# DRV8301_LaunchPad.net
KiCad netlist of a schematic drawn in Altium Designer
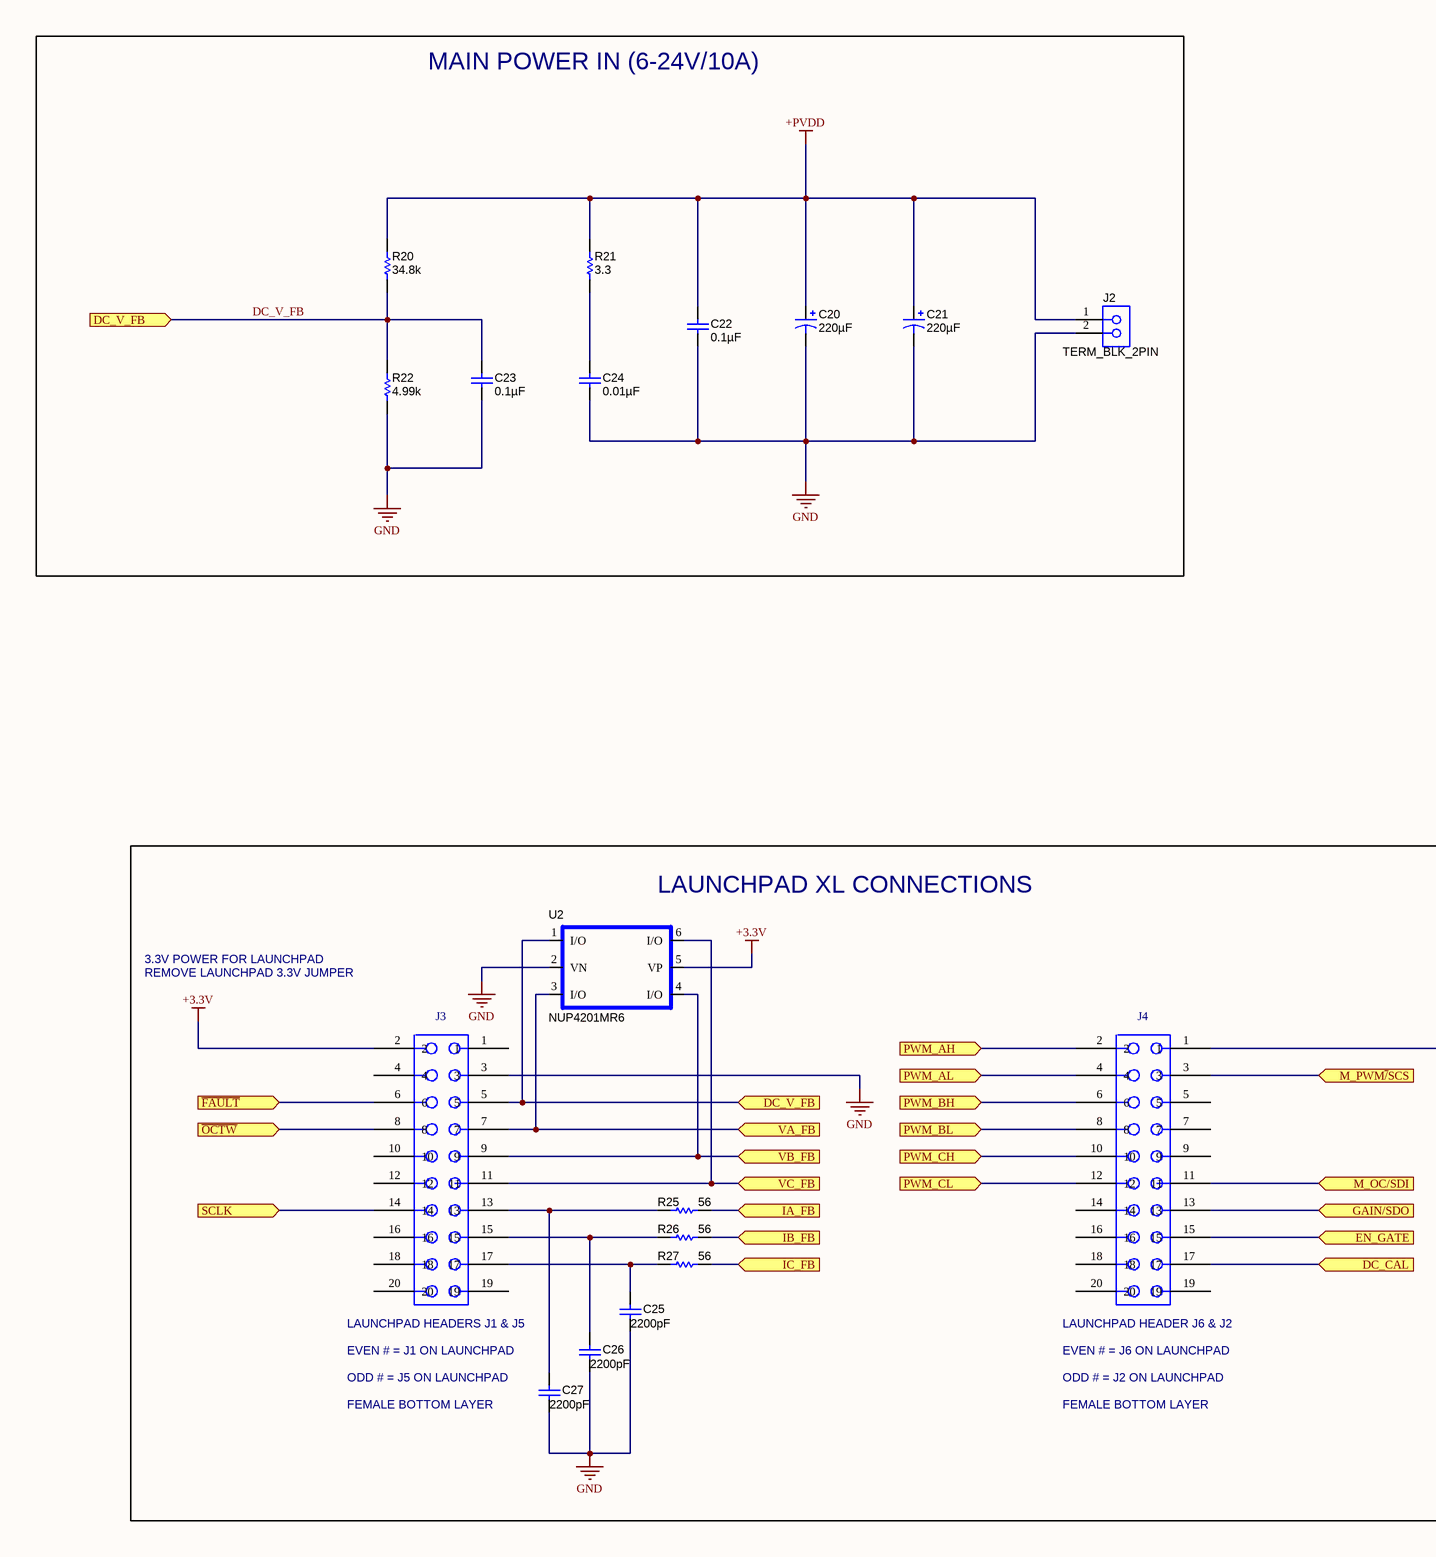
[diagram p0: DRV8301_LaunchPad.SchDoc, left]
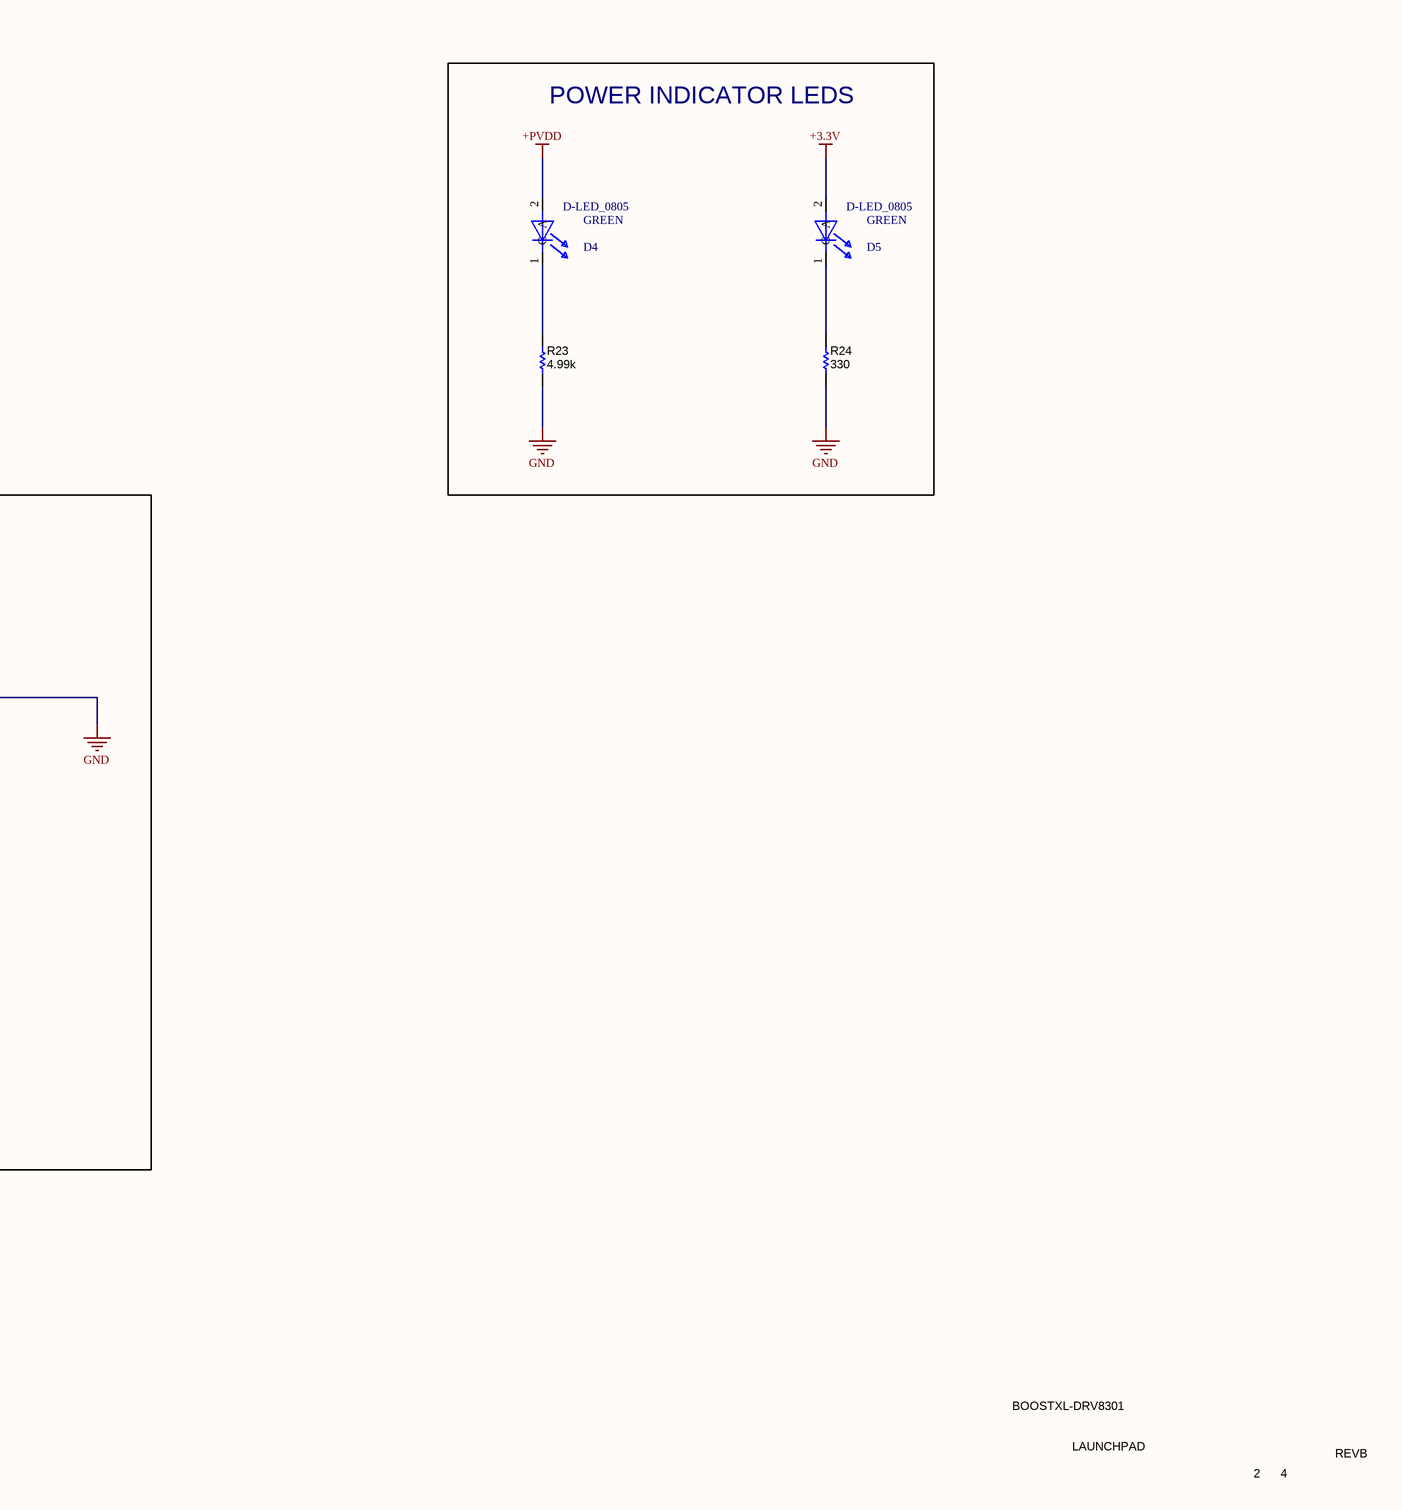
[diagram p1: DRV8301_LaunchPad.SchDoc, right]

(export (version "E")
  (design (tool "Eeschema 10.0.6"))
  (components
    (comp (ref "C20")
      (value "EEE-FC1H221P")
      (footprint "SM_RADIAL_G")
      (description "CAP, AL, 220uF, 50V, +/-20%, 0.3 ohm, SMD")
      (fields
        (field (name "VALUEDISPLAYED") "220µF")
        (field (name "MANUFACTURER") "Panasonic")
        (field (name "PUBLISHER") "Texas Instruments")
      )
      (libsource (lib "Capacitor_Aluminum") (part "EEE-FC1H221P"))
    )
    (comp (ref "C21")
      (value "EEE-FC1H221P")
      (footprint "SM_RADIAL_G")
      (description "CAP, AL, 220uF, 50V, +/-20%, 0.3 ohm, SMD")
      (fields
        (field (name "VALUEDISPLAYED") "220µF")
        (field (name "MANUFACTURER") "Panasonic")
        (field (name "PUBLISHER") "Texas Instruments")
      )
      (libsource (lib "Capacitor_Aluminum") (part "EEE-FC1H221P"))
    )
    (comp (ref "C22")
      (value "GRM188R72A104KA35D")
      (footprint "0603L")
      (description "CAP, CERM, 0.1uF, 100V, +/-10%, X7R, 0603")
      (fields
        (field (name "VALUEDISPLAYED") "0.1µF")
        (field (name "MANUFACTURER") "MuRata")
        (field (name "PUBLISHER") "Texas Instruments")
      )
      (libsource (lib "Capacitor_Ceramic") (part "GRM188R72A104KA35D"))
    )
    (comp (ref "C23")
      (value "C0603C104J4RACTU")
      (footprint "0603L")
      (description "CAP, CERM, 0.1uF, 16V, +/-5%, X7R, 0603")
      (fields
        (field (name "VALUEDISPLAYED") "0.1µF")
        (field (name "MANUFACTURER") "Kemet")
        (field (name "PUBLISHER") "Texas Instruments")
      )
      (libsource (lib "Capacitor_Ceramic") (part "C0603C104J4RACTU"))
    )
    (comp (ref "C24")
      (value "C1608X7R2A103K")
      (footprint "0603L")
      (description "CAP, CERM, 0.01uF, 100V, +/-10%, X7R, 0603")
      (fields
        (field (name "VALUEDISPLAYED") "0.01µF")
        (field (name "MANUFACTURER") "TDK")
        (field (name "PUBLISHER") "Texas Instruments")
      )
      (libsource (lib "Capacitor_Ceramic") (part "C1608X7R2A103K"))
    )
    (comp (ref "C25")
      (value "GRM188R71C222KA01D")
      (footprint "0603L")
      (description "CAP, CERM, 2200pF, 16V, +/-10%, X7R, 0603")
      (fields
        (field (name "VALUEDISPLAYED") "2200pF")
        (field (name "MANUFACTURER") "MuRata")
        (field (name "PUBLISHER") "Texas Instruments")
      )
      (libsource (lib "Capacitor_Ceramic") (part "GRM188R71C222KA01D"))
    )
    (comp (ref "C26")
      (value "GRM188R71C222KA01D")
      (footprint "0603L")
      (description "CAP, CERM, 2200pF, 16V, +/-10%, X7R, 0603")
      (fields
        (field (name "VALUEDISPLAYED") "2200pF")
        (field (name "MANUFACTURER") "MuRata")
        (field (name "PUBLISHER") "Texas Instruments")
      )
      (libsource (lib "Capacitor_Ceramic") (part "GRM188R71C222KA01D"))
    )
    (comp (ref "C27")
      (value "GRM188R71C222KA01D")
      (footprint "0603L")
      (description "CAP, CERM, 2200pF, 16V, +/-10%, X7R, 0603")
      (fields
        (field (name "VALUEDISPLAYED") "2200pF")
        (field (name "MANUFACTURER") "MuRata")
        (field (name "PUBLISHER") "Texas Instruments")
      )
      (libsource (lib "Capacitor_Ceramic") (part "GRM188R71C222KA01D"))
    )
    (comp (ref "D4")
      (value "D-LED_0805")
      (footprint "LED_0805")
      (description "LED THIN 565NM GRN DIFF 0805 SMD")
      (fields
        (field (name "PARTNUMBER") "SML-LXT0805GW-TR")
        (field (name "ALTIUM_VALUE") "GREEN")
        (field (name "MANUFACTURER") "Lumex Opto/Components Inc")
      )
      (libsource (lib "*") (part "D-LED_0805"))
    )
    (comp (ref "D5")
      (value "D-LED_0805")
      (footprint "LED_0805")
      (description "LED THIN 565NM GRN DIFF 0805 SMD")
      (fields
        (field (name "PARTNUMBER") "SML-LXT0805GW-TR")
        (field (name "ALTIUM_VALUE") "GREEN")
        (field (name "MANUFACTURER") "Lumex Opto/Components Inc")
      )
      (libsource (lib "*") (part "D-LED_0805"))
    )
    (comp (ref "J2")
      (value "TERM_BLK_2PIN")
      (footprint "CONN_ED120-2DS")
      (description "TERMINAL BLOCK 5.08MM VERT 2POS")
      (fields
        (field (name "PARTNUMBER") "OSTTA024163")
        (field (name "MANUFACTURER") "On-Shore Technology")
        (field (name "PUBLISHER") "Texas Instruments")
      )
      (libsource (lib "Connectors") (part "ED120/2DS"))
    )
    (comp (ref "J3")
      (value "HEADER_NPTC202KFM")
      (description "CONN RCPT 20POS .100 DL STR SMD")
      (fields (field (name "PARTNUMBER") "89898-310ALF") (field (name "MANUFACTURER") "FCI"))
      (libsource (lib "*") (part "HEADER_NPTC202KFM"))
    )
    (comp (ref "J4")
      (value "HEADER_NPTC202KFM")
      (description "CONN RCPT 20POS .100 DL STR SMD")
      (fields (field (name "PARTNUMBER") "89898-310ALF") (field (name "MANUFACTURER") "FCI"))
      (libsource (lib "*") (part "HEADER_NPTC202KFM"))
    )
    (comp (ref "R20")
      (value "34.8k")
      (footprint "0603L")
      (description "RES, 34.8k ohm, 1%, 0.1W, 0603")
      (fields
        (field (name "PARTNUMBER") "CRCW060334K8FKEA")
        (field (name "MANUFACTURER") "Vishay-Dale")
        (field (name "PUBLISHER") "Texas Instruments")
      )
      (libsource (lib "Resistor_0603") (part "CRCW060334K8FKEA"))
    )
    (comp (ref "R21")
      (value "3.3")
      (footprint "1206L")
      (description "RES, 3.3 ohm, 5%, 0.25W, 1206")
      (fields
        (field (name "PARTNUMBER") "CRCW12063R30JNEA")
        (field (name "MANUFACTURER") "Vishay-Dale")
        (field (name "PUBLISHER") "Texas Instruments")
      )
      (libsource (lib "Resistor_1206") (part "CRCW12063R30JNEA"))
    )
    (comp (ref "R22")
      (value "4.99k")
      (footprint "0603L")
      (description "RES, 4.99k ohm, 1%, 0.1W, 0603")
      (fields
        (field (name "PARTNUMBER") "CRCW06034K99FKEA")
        (field (name "MANUFACTURER") "Vishay-Dale")
        (field (name "PUBLISHER") "Texas Instruments")
      )
      (libsource (lib "Resistor_0603") (part "CRCW06034K99FKEA"))
    )
    (comp (ref "R23")
      (value "4.99k")
      (footprint "0603L")
      (description "RES, 4.99k ohm, 1%, 0.1W, 0603")
      (fields
        (field (name "PARTNUMBER") "CRCW06034K99FKEA")
        (field (name "MANUFACTURER") "Vishay-Dale")
        (field (name "PUBLISHER") "Texas Instruments")
      )
      (libsource (lib "Resistor_0603") (part "CRCW06034K99FKEA"))
    )
    (comp (ref "R24")
      (value "330")
      (footprint "0603L")
      (description "RES, 330 ohm, 5%, 0.1W, 0603")
      (fields
        (field (name "PARTNUMBER") "CRCW0603330RJNEA")
        (field (name "MANUFACTURER") "Vishay-Dale")
        (field (name "PUBLISHER") "Texas Instruments")
      )
      (libsource (lib "Resistor_0603") (part "CRCW0603330RJNEA"))
    )
    (comp (ref "R25")
      (value "56")
      (footprint "0603L")
      (description "RES, 56 ohm, 5%, 0.1W, 0603")
      (fields
        (field (name "PARTNUMBER") "CRCW060356R0JNEA")
        (field (name "MANUFACTURER") "Vishay-Dale")
        (field (name "PUBLISHER") "Texas Instruments")
      )
      (libsource (lib "Resistor_0603") (part "CRCW060356R0JNEA"))
    )
    (comp (ref "R26")
      (value "56")
      (footprint "0603L")
      (description "RES, 56 ohm, 5%, 0.1W, 0603")
      (fields
        (field (name "PARTNUMBER") "CRCW060356R0JNEA")
        (field (name "MANUFACTURER") "Vishay-Dale")
        (field (name "PUBLISHER") "Texas Instruments")
      )
      (libsource (lib "Resistor_0603") (part "CRCW060356R0JNEA"))
    )
    (comp (ref "R27")
      (value "56")
      (footprint "0603L")
      (description "RES, 56 ohm, 5%, 0.1W, 0603")
      (fields
        (field (name "PARTNUMBER") "CRCW060356R0JNEA")
        (field (name "MANUFACTURER") "Vishay-Dale")
        (field (name "PUBLISHER") "Texas Instruments")
      )
      (libsource (lib "Resistor_0603") (part "CRCW060356R0JNEA"))
    )
    (comp (ref "U2")
      (value "NUP4201MR6")
      (footprint "SOT23-6")
      (description "IC,  500w 6v, Transient Voltage  Suppressors")
      (fields (field (name "MANUFACTURER") "On Semi"))
      (libsource (lib "PADSlegacy_PMP") (part "NUP4201MR6"))
    )
  )
  (nets
    (net (code "1") (name "+3.3V") (class "Default")
      (node (ref "D5") (pin "2") (pinfunction "A_2") (pintype "passive"))
      (node (ref "J3") (pin "2") (pinfunction "2_2") (pintype "passive"))
      (node (ref "U2") (pin "5") (pinfunction "VP_5") (pintype "passive"))
    )
    (net (code "2") (name "+PVDD") (class "Default")
      (node (ref "C20") (pin "1") (pinfunction "+_1") (pintype "passive"))
      (node (ref "C21") (pin "1") (pinfunction "+_1") (pintype "passive"))
      (node (ref "C22") (pin "1") (pinfunction "1_1") (pintype "passive"))
      (node (ref "D4") (pin "2") (pinfunction "A_2") (pintype "passive"))
      (node (ref "J2") (pin "1") (pinfunction "1_1") (pintype "passive"))
      (node (ref "R20") (pin "2") (pinfunction "2_2") (pintype "passive"))
      (node (ref "R21") (pin "2") (pinfunction "2_2") (pintype "passive"))
    )
    (net (code "3") (name "/DC_CAL") (class "Default")
      (node (ref "J4") (pin "17") (pinfunction "17_17") (pintype "passive"))
    )
    (net (code "4") (name "/DC_V_FB") (class "Default")
      (node (ref "C23") (pin "1") (pinfunction "1_1") (pintype "passive"))
      (node (ref "J3") (pin "5") (pinfunction "5_5") (pintype "passive"))
      (node (ref "R20") (pin "1") (pinfunction "1_1") (pintype "passive"))
      (node (ref "R22") (pin "2") (pinfunction "2_2") (pintype "passive"))
      (node (ref "U2") (pin "1") (pinfunction "I/O_1") (pintype "passive"))
    )
    (net (code "5") (name "/EN_GATE") (class "Default")
      (node (ref "J4") (pin "15") (pinfunction "15_15") (pintype "passive"))
    )
    (net (code "6") (name "/FAULT") (class "Default")
      (node (ref "J3") (pin "6") (pinfunction "6_6") (pintype "passive"))
    )
    (net (code "7") (name "/GAIN{slash}SDO") (class "Default")
      (node (ref "J4") (pin "13") (pinfunction "13_13") (pintype "passive"))
    )
    (net (code "8") (name "/IA_FB") (class "Default")
      (node (ref "R25") (pin "2") (pinfunction "2_2") (pintype "passive"))
    )
    (net (code "9") (name "/IB_FB") (class "Default")
      (node (ref "R26") (pin "2") (pinfunction "2_2") (pintype "passive"))
    )
    (net (code "10") (name "/IC_FB") (class "Default")
      (node (ref "R27") (pin "2") (pinfunction "2_2") (pintype "passive"))
    )
    (net (code "11") (name "/M_OC{slash}SDI") (class "Default")
      (node (ref "J4") (pin "11") (pinfunction "11_11") (pintype "passive"))
    )
    (net (code "12") (name "/M_PWM~{{slash}}SCS") (class "Default")
      (node (ref "J4") (pin "3") (pinfunction "3_3") (pintype "passive"))
    )
    (net (code "13") (name "/OCTW") (class "Default")
      (node (ref "J3") (pin "8") (pinfunction "8_8") (pintype "passive"))
    )
    (net (code "14") (name "/PWM_AH") (class "Default")
      (node (ref "J4") (pin "2") (pinfunction "2_2") (pintype "passive"))
    )
    (net (code "15") (name "/PWM_AL") (class "Default")
      (node (ref "J4") (pin "4") (pinfunction "4_4") (pintype "passive"))
    )
    (net (code "16") (name "/PWM_BH") (class "Default")
      (node (ref "J4") (pin "6") (pinfunction "6_6") (pintype "passive"))
    )
    (net (code "17") (name "/PWM_BL") (class "Default")
      (node (ref "J4") (pin "8") (pinfunction "8_8") (pintype "passive"))
    )
    (net (code "18") (name "/PWM_CH") (class "Default")
      (node (ref "J4") (pin "10") (pinfunction "10_10") (pintype "passive"))
    )
    (net (code "19") (name "/PWM_CL") (class "Default")
      (node (ref "J4") (pin "12") (pinfunction "12_12") (pintype "passive"))
    )
    (net (code "20") (name "/SCLK") (class "Default")
      (node (ref "J3") (pin "14") (pinfunction "14_14") (pintype "passive"))
    )
    (net (code "21") (name "/VA_FB") (class "Default")
      (node (ref "J3") (pin "7") (pinfunction "7_7") (pintype "passive"))
      (node (ref "U2") (pin "3") (pinfunction "I/O_3") (pintype "passive"))
    )
    (net (code "22") (name "/VB_FB") (class "Default")
      (node (ref "J3") (pin "9") (pinfunction "9_9") (pintype "passive"))
      (node (ref "U2") (pin "4") (pinfunction "I/O_4") (pintype "passive"))
    )
    (net (code "23") (name "/VC_FB") (class "Default")
      (node (ref "J3") (pin "11") (pinfunction "11_11") (pintype "passive"))
      (node (ref "U2") (pin "6") (pinfunction "I/O_6") (pintype "passive"))
    )
    (net (code "24") (name "GND") (class "Default")
      (node (ref "C20") (pin "2") (pinfunction "-_2") (pintype "passive"))
      (node (ref "C21") (pin "2") (pinfunction "-_2") (pintype "passive"))
      (node (ref "C22") (pin "2") (pinfunction "2_2") (pintype "passive"))
      (node (ref "C23") (pin "2") (pinfunction "2_2") (pintype "passive"))
      (node (ref "C24") (pin "2") (pinfunction "2_2") (pintype "passive"))
      (node (ref "C25") (pin "2") (pinfunction "2_2") (pintype "passive"))
      (node (ref "C26") (pin "2") (pinfunction "2_2") (pintype "passive"))
      (node (ref "C27") (pin "2") (pinfunction "2_2") (pintype "passive"))
      (node (ref "J2") (pin "2") (pinfunction "2_2") (pintype "passive"))
      (node (ref "J3") (pin "3") (pinfunction "3_3") (pintype "passive"))
      (node (ref "J4") (pin "1") (pinfunction "1_1") (pintype "passive"))
      (node (ref "R22") (pin "1") (pinfunction "1_1") (pintype "passive"))
      (node (ref "R23") (pin "1") (pinfunction "1_1") (pintype "passive"))
      (node (ref "R24") (pin "1") (pinfunction "1_1") (pintype "passive"))
      (node (ref "U2") (pin "2") (pinfunction "VN_2") (pintype "passive"))
    )
    (net (code "25") (name "Net-(C24-Pad1)") (class "Default")
      (node (ref "C24") (pin "1") (pinfunction "1_1") (pintype "passive"))
      (node (ref "R21") (pin "1") (pinfunction "1_1") (pintype "passive"))
    )
    (net (code "26") (name "Net-(C25-Pad1)") (class "Default")
      (node (ref "C25") (pin "1") (pinfunction "1_1") (pintype "passive"))
      (node (ref "J3") (pin "17") (pinfunction "17_17") (pintype "passive"))
      (node (ref "R27") (pin "1") (pinfunction "1_1") (pintype "passive"))
    )
    (net (code "27") (name "Net-(C26-Pad1)") (class "Default")
      (node (ref "C26") (pin "1") (pinfunction "1_1") (pintype "passive"))
      (node (ref "J3") (pin "15") (pinfunction "15_15") (pintype "passive"))
      (node (ref "R26") (pin "1") (pinfunction "1_1") (pintype "passive"))
    )
    (net (code "28") (name "Net-(C27-Pad1)") (class "Default")
      (node (ref "C27") (pin "1") (pinfunction "1_1") (pintype "passive"))
      (node (ref "J3") (pin "13") (pinfunction "13_13") (pintype "passive"))
      (node (ref "R25") (pin "1") (pinfunction "1_1") (pintype "passive"))
    )
    (net (code "29") (name "Net-(D4-C)") (class "Default")
      (node (ref "D4") (pin "1") (pinfunction "C_1") (pintype "passive"))
      (node (ref "R23") (pin "2") (pinfunction "2_2") (pintype "passive"))
    )
    (net (code "30") (name "Net-(D5-C)") (class "Default")
      (node (ref "D5") (pin "1") (pinfunction "C_1") (pintype "passive"))
      (node (ref "R24") (pin "2") (pinfunction "2_2") (pintype "passive"))
    )
    (net (code "31") (name "unconnected-(J3-Pad1)") (class "Default")
      (node (ref "J3") (pin "1") (pinfunction "1_1") (pintype "passive"))
    )
    (net (code "32") (name "unconnected-(J3-Pad4)") (class "Default")
      (node (ref "J3") (pin "4") (pinfunction "4_4") (pintype "passive"))
    )
    (net (code "33") (name "unconnected-(J3-Pad10)") (class "Default")
      (node (ref "J3") (pin "10") (pinfunction "10_10") (pintype "passive"))
    )
    (net (code "34") (name "unconnected-(J3-Pad12)") (class "Default")
      (node (ref "J3") (pin "12") (pinfunction "12_12") (pintype "passive"))
    )
    (net (code "35") (name "unconnected-(J3-Pad16)") (class "Default")
      (node (ref "J3") (pin "16") (pinfunction "16_16") (pintype "passive"))
    )
    (net (code "36") (name "unconnected-(J3-Pad18)") (class "Default")
      (node (ref "J3") (pin "18") (pinfunction "18_18") (pintype "passive"))
    )
    (net (code "37") (name "unconnected-(J3-Pad19)") (class "Default")
      (node (ref "J3") (pin "19") (pinfunction "19_19") (pintype "passive"))
    )
    (net (code "38") (name "unconnected-(J3-Pad20)") (class "Default")
      (node (ref "J3") (pin "20") (pinfunction "20_20") (pintype "passive"))
    )
    (net (code "39") (name "unconnected-(J4-Pad5)") (class "Default")
      (node (ref "J4") (pin "5") (pinfunction "5_5") (pintype "passive"))
    )
    (net (code "40") (name "unconnected-(J4-Pad7)") (class "Default")
      (node (ref "J4") (pin "7") (pinfunction "7_7") (pintype "passive"))
    )
    (net (code "41") (name "unconnected-(J4-Pad9)") (class "Default")
      (node (ref "J4") (pin "9") (pinfunction "9_9") (pintype "passive"))
    )
    (net (code "42") (name "unconnected-(J4-Pad14)") (class "Default")
      (node (ref "J4") (pin "14") (pinfunction "14_14") (pintype "passive"))
    )
    (net (code "43") (name "unconnected-(J4-Pad16)") (class "Default")
      (node (ref "J4") (pin "16") (pinfunction "16_16") (pintype "passive"))
    )
    (net (code "44") (name "unconnected-(J4-Pad18)") (class "Default")
      (node (ref "J4") (pin "18") (pinfunction "18_18") (pintype "passive"))
    )
    (net (code "45") (name "unconnected-(J4-Pad19)") (class "Default")
      (node (ref "J4") (pin "19") (pinfunction "19_19") (pintype "passive"))
    )
    (net (code "46") (name "unconnected-(J4-Pad20)") (class "Default")
      (node (ref "J4") (pin "20") (pinfunction "20_20") (pintype "passive"))
    )
  )
)
